# SparkFun_Qwiic_Distance_-_VL53L4CD.net
KiCad netlist of a schematic drawn in EAGLE
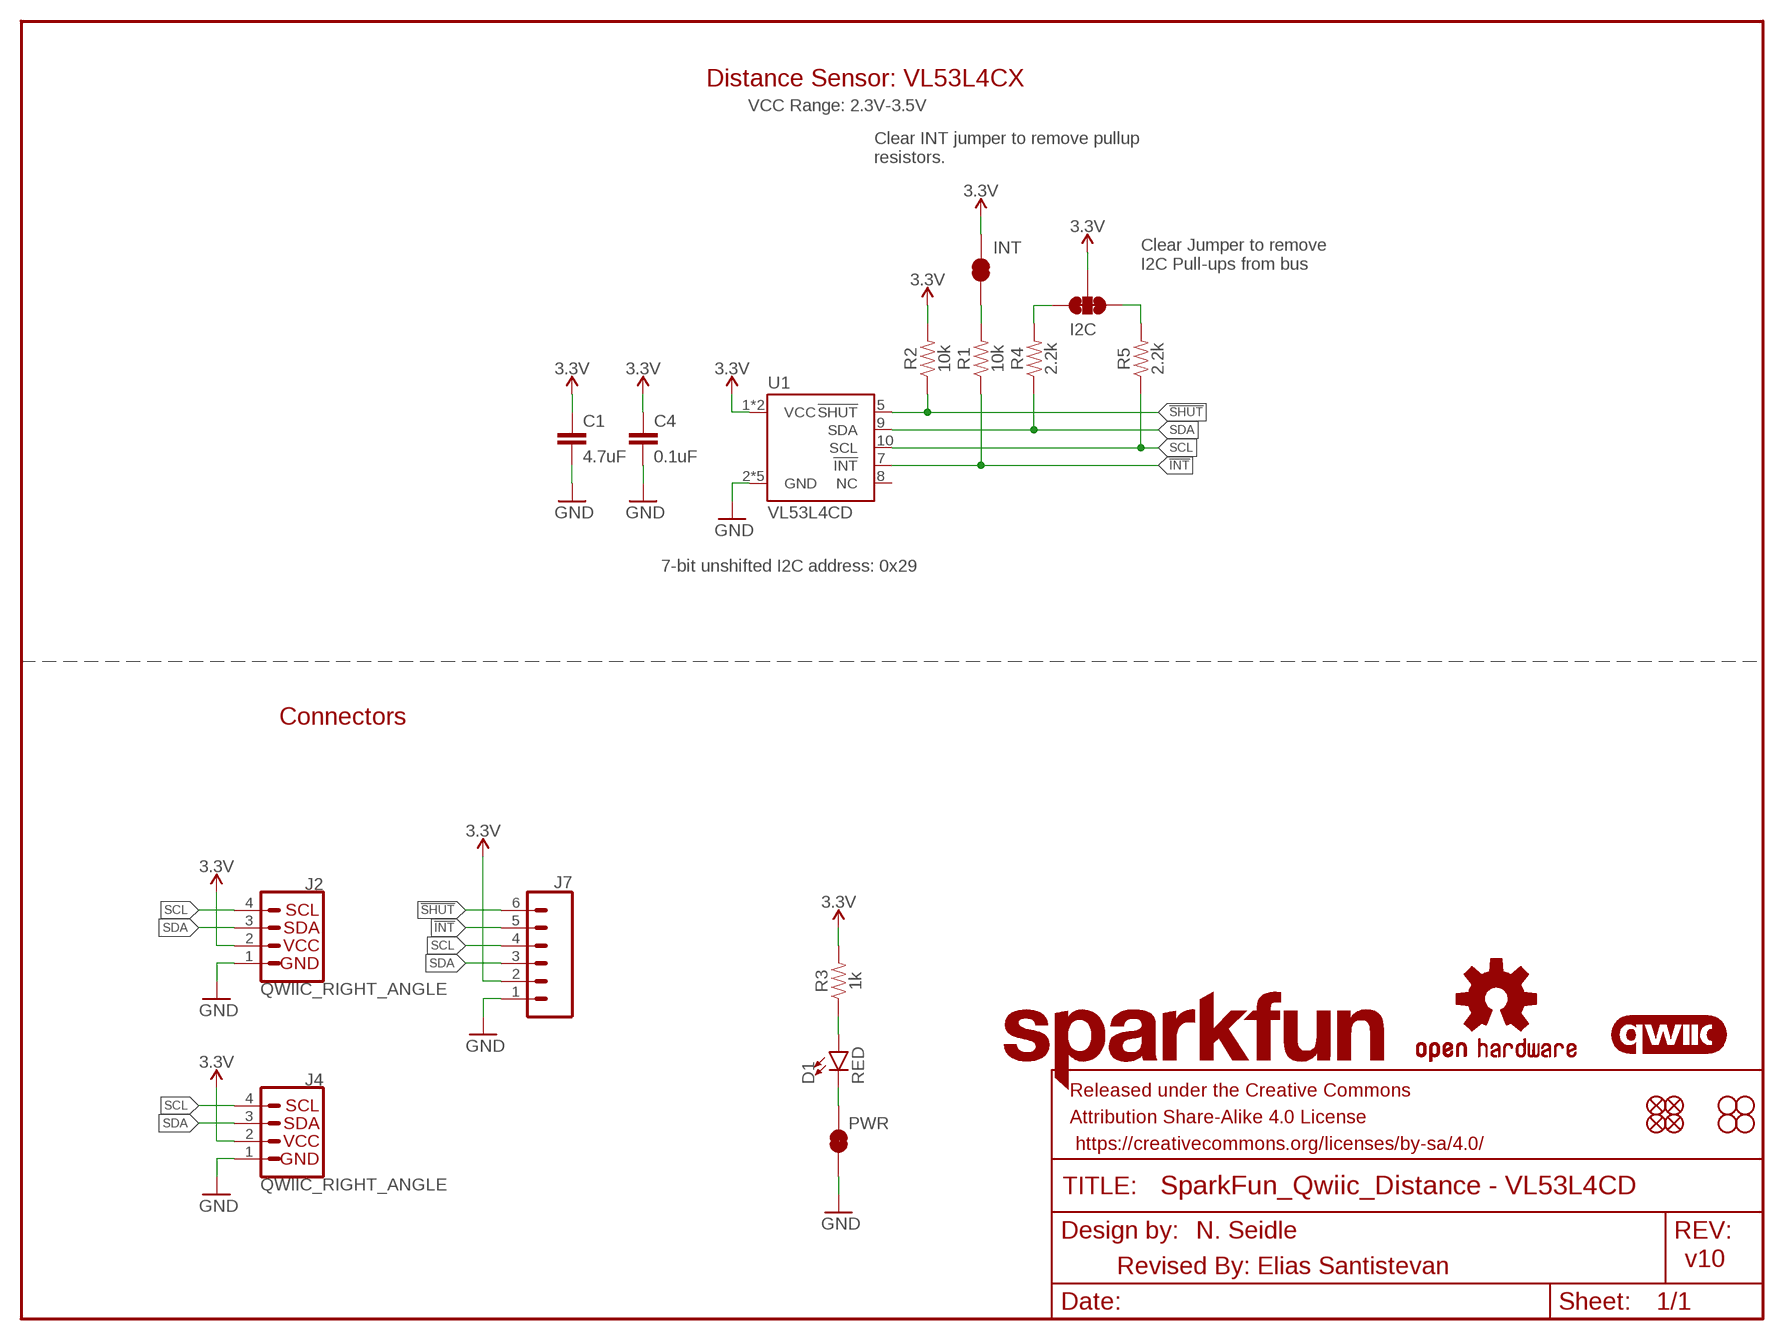
[diagram p0: schematic, sheet 1]

(export (version "E")
  (design (tool "Eeschema 10.0.6"))
  (components
    (comp (ref "C1")
      (value "4.7uF")
      (footprint "eagle-import:0603")
      (libsource (lib "eagle-import") (part "4.7UF-0603-6.3V-(10%)"))
    )
    (comp (ref "C4")
      (value "0.1uF")
      (footprint "eagle-import:0603")
      (libsource (lib "eagle-import") (part "0.1UF-0603-25V-(+80/-20%)"))
    )
    (comp (ref "D1")
      (value "RED")
      (footprint "eagle-import:LED-0603")
      (libsource (lib "eagle-import") (part "LED-RED0603"))
    )
    (comp (ref "FRAME1")
      (value "FRAME-LETTER")
      (footprint "eagle-import:CREATIVE_COMMONS")
      (libsource (lib "eagle-import") (part "FRAME-LETTER"))
    )
    (comp (ref "I2C")
      (value "JUMPER-SMT_3_2-NC_TRACE_SILK")
      (footprint "eagle-import:SMT-JUMPER_3_2-NC_TRACE_SILK")
      (libsource (lib "eagle-import") (part "JUMPER-SMT_3_2-NC_TRACE_SILK"))
    )
    (comp (ref "J2")
      (value "QWIIC_RIGHT_ANGLE")
      (footprint "eagle-import:JST04_1MM_RA")
      (libsource (lib "eagle-import") (part "QWIIC_CONNECTORJS-1MM"))
    )
    (comp (ref "J4")
      (value "QWIIC_RIGHT_ANGLE")
      (footprint "eagle-import:JST04_1MM_RA")
      (libsource (lib "eagle-import") (part "QWIIC_CONNECTORJS-1MM"))
    )
    (comp (ref "J7")
      (value "CONN_06NO_SILK_NO_POP")
      (footprint "eagle-import:1X06_NO_SILK")
      (libsource (lib "eagle-import") (part "CONN_06NO_SILK_NO_POP"))
    )
    (comp (ref "JP1")
      (value "FIDUCIALUFIDUCIAL")
      (footprint "eagle-import:MICRO-FIDUCIAL")
      (libsource (lib "eagle-import") (part "FIDUCIALUFIDUCIAL"))
    )
    (comp (ref "JP2")
      (value "FIDUCIALUFIDUCIAL")
      (footprint "eagle-import:MICRO-FIDUCIAL")
      (libsource (lib "eagle-import") (part "FIDUCIALUFIDUCIAL"))
    )
    (comp (ref "JP3")
      (value "STAND-OFF")
      (footprint "eagle-import:STAND-OFF")
      (libsource (lib "eagle-import") (part "STAND-OFF"))
    )
    (comp (ref "JP4")
      (value "STAND-OFF")
      (footprint "eagle-import:STAND-OFF")
      (libsource (lib "eagle-import") (part "STAND-OFF"))
    )
    (comp (ref "JP5")
      (value "FIDUCIALUFIDUCIAL")
      (footprint "eagle-import:MICRO-FIDUCIAL")
      (libsource (lib "eagle-import") (part "FIDUCIALUFIDUCIAL"))
    )
    (comp (ref "JP6")
      (value "FIDUCIALUFIDUCIAL")
      (footprint "eagle-import:MICRO-FIDUCIAL")
      (libsource (lib "eagle-import") (part "FIDUCIALUFIDUCIAL"))
    )
    (comp (ref "JP7")
      (value "STAND-OFF")
      (footprint "eagle-import:STAND-OFF")
      (libsource (lib "eagle-import") (part "STAND-OFF"))
    )
    (comp (ref "JP8")
      (value "STAND-OFF")
      (footprint "eagle-import:STAND-OFF")
      (libsource (lib "eagle-import") (part "STAND-OFF"))
    )
    (comp (ref "JP9")
      (value "INT")
      (footprint "eagle-import:SMT-JUMPER_2_NC_TRACE_SILK")
      (libsource (lib "eagle-import") (part "JUMPER-SMT_2_NC_TRACE_SILK"))
    )
    (comp (ref "LOGO1")
      (value "OSHW-LOGOMINI")
      (footprint "eagle-import:OSHW-LOGO-MINI")
      (libsource (lib "eagle-import") (part "OSHW-LOGOMINI"))
    )
    (comp (ref "LOGO2")
      (value "SFE_LOGO_NAME.1_INCH")
      (footprint "eagle-import:SFE_LOGO_NAME_.1")
      (libsource (lib "eagle-import") (part "SFE_LOGO_NAME.1_INCH"))
    )
    (comp (ref "LOGO3")
      (value "QWIIC_LOGO_4MM")
      (footprint "eagle-import:QWIIC_4MM")
      (libsource (lib "eagle-import") (part "QWIIC_LOGO_4MM"))
    )
    (comp (ref "PWR")
      (value "INT")
      (footprint "eagle-import:SMT-JUMPER_2_NC_TRACE_SILK")
      (libsource (lib "eagle-import") (part "JUMPER-SMT_2_NC_TRACE_SILK"))
    )
    (comp (ref "R1")
      (value "10k")
      (footprint "eagle-import:0603")
      (libsource (lib "eagle-import") (part "10KOHM-0603-1/10W-1%"))
    )
    (comp (ref "R2")
      (value "10k")
      (footprint "eagle-import:0603")
      (libsource (lib "eagle-import") (part "10KOHM-0603-1/10W-1%"))
    )
    (comp (ref "R3")
      (value "1k")
      (footprint "eagle-import:0603")
      (libsource (lib "eagle-import") (part "1KOHM-0603-1/10W-1%"))
    )
    (comp (ref "R4")
      (value "2.2k")
      (footprint "eagle-import:0603")
      (libsource (lib "eagle-import") (part "2.2KOHM-0603-1/10W-1%"))
    )
    (comp (ref "R5")
      (value "2.2k")
      (footprint "eagle-import:0603")
      (libsource (lib "eagle-import") (part "2.2KOHM-0603-1/10W-1%"))
    )
    (comp (ref "U1")
      (value "VL53L4CD")
      (footprint "eagle-import:VL53L4CD")
      (libsource (lib "eagle-import") (part "VL53L4CD"))
    )
  )
  (nets
    (net (code "1") (name "/~{INT}") (class "Default")
      (node (ref "J7") (pin "5") (pinfunction "5_5") (pintype "passive"))
      (node (ref "R1") (pin "1") (pinfunction "1_1") (pintype "passive"))
      (node (ref "U1") (pin "7") (pinfunction "~{INT}_7") (pintype "output"))
    )
    (net (code "2") (name "/~{SHUT}") (class "Default")
      (node (ref "J7") (pin "6") (pinfunction "6_6") (pintype "passive"))
      (node (ref "R2") (pin "1") (pinfunction "1_1") (pintype "passive"))
      (node (ref "U1") (pin "5") (pinfunction "~{SHUT}_5") (pintype "input"))
    )
    (net (code "3") (name "3.3V") (class "Default")
      (node (ref "C1") (pin "1") (pinfunction "1_1") (pintype "passive"))
      (node (ref "C4") (pin "1") (pinfunction "1_1") (pintype "passive"))
      (node (ref "I2C") (pin "2") (pinfunction "2_2") (pintype "passive"))
      (node (ref "J2") (pin "2") (pinfunction "2_2") (pintype "power_in"))
      (node (ref "J4") (pin "2") (pinfunction "2_2") (pintype "power_in"))
      (node (ref "J7") (pin "2") (pinfunction "2_2") (pintype "passive"))
      (node (ref "JP9") (pin "2") (pinfunction "2_2") (pintype "passive"))
      (node (ref "R2") (pin "2") (pinfunction "2_2") (pintype "passive"))
      (node (ref "R3") (pin "2") (pinfunction "2_2") (pintype "passive"))
      (node (ref "U1") (pin "1") (pinfunction "VCC_1") (pintype "power_in"))
      (node (ref "U1") (pin "11") (pinfunction "VCC_11") (pintype "power_in"))
    )
    (net (code "4") (name "GND") (class "Default")
      (node (ref "C1") (pin "2") (pinfunction "2_2") (pintype "passive"))
      (node (ref "C4") (pin "2") (pinfunction "2_2") (pintype "passive"))
      (node (ref "J2") (pin "1") (pinfunction "1_1") (pintype "power_in"))
      (node (ref "J4") (pin "1") (pinfunction "1_1") (pintype "power_in"))
      (node (ref "J7") (pin "1") (pinfunction "1_1") (pintype "passive"))
      (node (ref "PWR") (pin "1") (pinfunction "1_1") (pintype "passive"))
      (node (ref "U1") (pin "12") (pinfunction "GND_12") (pintype "power_in"))
      (node (ref "U1") (pin "2") (pinfunction "GND_2") (pintype "power_in"))
      (node (ref "U1") (pin "3") (pinfunction "GND_3") (pintype "power_in"))
      (node (ref "U1") (pin "4") (pinfunction "GND_4") (pintype "power_in"))
      (node (ref "U1") (pin "6") (pinfunction "GND_6") (pintype "power_in"))
    )
    (net (code "5") (name "Net-(D1-PadA)") (class "Default")
      (node (ref "D1") (pin "A") (pinfunction "A_A") (pintype "passive"))
      (node (ref "R3") (pin "1") (pinfunction "1_1") (pintype "passive"))
    )
    (net (code "6") (name "Net-(D1-PadC)") (class "Default")
      (node (ref "D1") (pin "C") (pinfunction "C_C") (pintype "passive"))
      (node (ref "PWR") (pin "2") (pinfunction "2_2") (pintype "passive"))
    )
    (net (code "7") (name "Net-(I2C-Pad1)") (class "Default")
      (node (ref "I2C") (pin "1") (pinfunction "1_1") (pintype "passive"))
      (node (ref "R5") (pin "2") (pinfunction "2_2") (pintype "passive"))
    )
    (net (code "8") (name "Net-(I2C-Pad3)") (class "Default")
      (node (ref "I2C") (pin "3") (pinfunction "3_3") (pintype "passive"))
      (node (ref "R4") (pin "2") (pinfunction "2_2") (pintype "passive"))
    )
    (net (code "9") (name "Net-(JP9-Pad1)") (class "Default")
      (node (ref "JP9") (pin "1") (pinfunction "1_1") (pintype "passive"))
      (node (ref "R1") (pin "2") (pinfunction "2_2") (pintype "passive"))
    )
    (net (code "10") (name "SCL") (class "Default")
      (node (ref "J2") (pin "4") (pinfunction "4_4") (pintype "passive"))
      (node (ref "J4") (pin "4") (pinfunction "4_4") (pintype "passive"))
      (node (ref "J7") (pin "4") (pinfunction "4_4") (pintype "passive"))
      (node (ref "R5") (pin "1") (pinfunction "1_1") (pintype "passive"))
      (node (ref "U1") (pin "10") (pinfunction "SCL_10") (pintype "bidirectional"))
    )
    (net (code "11") (name "SDA") (class "Default")
      (node (ref "J2") (pin "3") (pinfunction "3_3") (pintype "passive"))
      (node (ref "J4") (pin "3") (pinfunction "3_3") (pintype "passive"))
      (node (ref "J7") (pin "3") (pinfunction "3_3") (pintype "passive"))
      (node (ref "R4") (pin "1") (pinfunction "1_1") (pintype "passive"))
      (node (ref "U1") (pin "9") (pinfunction "SDA_9") (pintype "bidirectional"))
    )
    (net (code "12") (name "unconnected-(U1-NC-Pad8)") (class "Default")
      (node (ref "U1") (pin "8") (pinfunction "NC_8") (pintype "no_connect"))
    )
  )
)
